# Power.net
KiCad netlist of a schematic drawn in Altium Designer
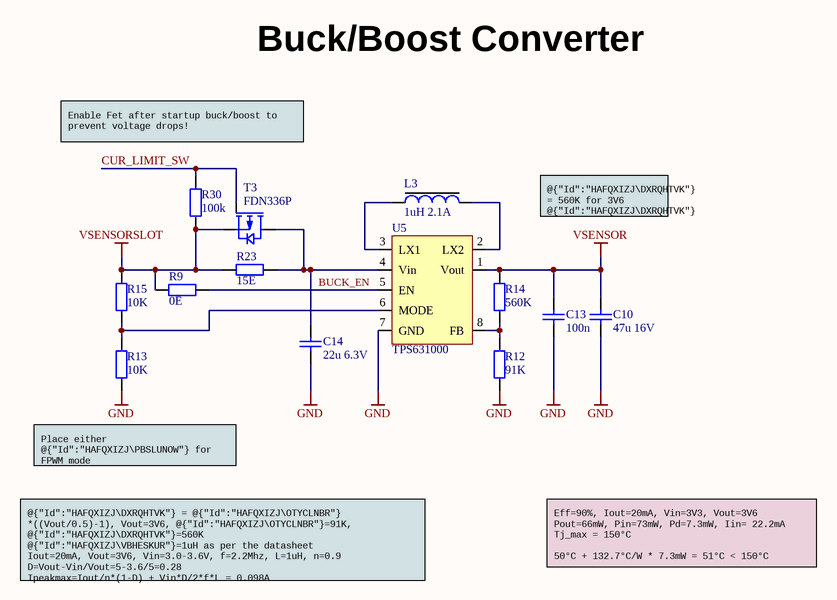
[diagram p0: Power.SchDoc]

(export (version "E")
  (design (tool "Eeschema 10.0.6"))
  (components
    (comp (ref "C10")
      (value "47u 16V")
      (footprint "CAPC3225X27N")
      (description "47uF 16V 20% X5R")
      (libsource (lib "DCI") (part "Capacitor_NP"))
    )
    (comp (ref "C13")
      (value "100n")
      (footprint "CAPC1608X09N")
      (description "100nF 50V 10% X7R")
      (libsource (lib "DCI") (part "Capacitor_NP"))
    )
    (comp (ref "C14")
      (value "22u 6.3V")
      (footprint "CAPC1608X09N")
      (description "22uF 20%  6.3V X5R")
      (libsource (lib "DCI") (part "Capacitor_NP"))
    )
    (comp (ref "L3")
      (value "1uH 2.1A")
      (footprint "IND-001G002-002")
      (description "Power inductor 2.1A")
      (libsource (lib "DCI") (part "Inductor"))
    )
    (comp (ref "R9")
      (value "0E")
      (footprint "RESC1608X13N")
      (description "0E 100mW, 1%")
      (libsource (lib "") (part "Resistor_2"))
    )
    (comp (ref "R12")
      (value "91K")
      (footprint "RESC1608X13N")
      (description "91k 0.06W 1%")
      (libsource (lib "") (part "Resistor_1"))
    )
    (comp (ref "R13")
      (value "10K")
      (footprint "RESC1608X13N")
      (description "10k 100mW, 1%")
      (libsource (lib "") (part "Resistor_1"))
    )
    (comp (ref "R14")
      (value "560K")
      (footprint "RESC1608X13N")
      (description "560kΩ 100mW 1%")
      (libsource (lib "DCI") (part "Resistor"))
    )
    (comp (ref "R15")
      (value "10K")
      (footprint "RESC1608X13N")
      (description "10k 100mW, 1%")
      (libsource (lib "") (part "Resistor_1"))
    )
    (comp (ref "R23")
      (value "15E")
      (footprint "RESC2013X14N")
      (description "15Ω 125mW 1%")
      (libsource (lib "") (part "Resistor_3"))
    )
    (comp (ref "R30")
      (value "100k")
      (footprint "RESC1608X13N")
      (description "100kΩ 100mW 1%")
      (libsource (lib "DCI") (part "Resistor"))
    )
    (comp (ref "T3")
      (value "FDN336P")
      (footprint "SOT95P245X110_GSD-3N")
      (description "20V 1.3A 200mΩ logic level")
      (libsource (lib "DCI") (part "P_Mosfet"))
    )
    (comp (ref "U5")
      (value "TPS631000")
      (footprint "SOT-501001-008")
      (description "Buck/boost 1.5-5.5V, 1A5")
      (libsource (lib "DCI") (part "SW_BUCK_BOOST_TPS631000"))
    )
  )
  (nets
    (net (code "1") (name "/BUCK_EN") (class "Default")
      (node (ref "R9") (pin "1") (pinfunction "1_1") (pintype "passive"))
      (node (ref "U5") (pin "5") (pinfunction "EN_5") (pintype "passive"))
    )
    (net (code "2") (name "/CUR_LIMIT_SW") (class "Default")
      (node (ref "R30") (pin "2") (pinfunction "2_2") (pintype "passive"))
      (node (ref "T3") (pin "G") (pinfunction "G_G") (pintype "passive"))
    )
    (net (code "3") (name "GND") (class "Default")
      (node (ref "C10") (pin "1") (pinfunction "1_1") (pintype "passive"))
      (node (ref "C13") (pin "1") (pinfunction "1_1") (pintype "passive"))
      (node (ref "C14") (pin "1") (pinfunction "1_1") (pintype "passive"))
      (node (ref "R12") (pin "1") (pinfunction "1_1") (pintype "passive"))
      (node (ref "R13") (pin "1") (pinfunction "1_1") (pintype "passive"))
      (node (ref "U5") (pin "7") (pinfunction "GND_7") (pintype "passive"))
    )
    (net (code "4") (name "Net-(U5-FB)") (class "Default")
      (node (ref "R12") (pin "2") (pinfunction "2_2") (pintype "passive"))
      (node (ref "R14") (pin "1") (pinfunction "1_1") (pintype "passive"))
      (node (ref "U5") (pin "8") (pinfunction "FB_8") (pintype "passive"))
    )
    (net (code "5") (name "Net-(U5-LX1)") (class "Default")
      (node (ref "L3") (pin "1") (pinfunction "1_1") (pintype "passive"))
      (node (ref "U5") (pin "3") (pinfunction "LX1_3") (pintype "power_in"))
    )
    (net (code "6") (name "Net-(U5-LX2)") (class "Default")
      (node (ref "L3") (pin "2") (pinfunction "2_2") (pintype "passive"))
      (node (ref "U5") (pin "2") (pinfunction "LX2_2") (pintype "power_in"))
    )
    (net (code "7") (name "Net-(U5-MODE)") (class "Default")
      (node (ref "R13") (pin "2") (pinfunction "2_2") (pintype "passive"))
      (node (ref "R15") (pin "1") (pinfunction "1_1") (pintype "passive"))
      (node (ref "U5") (pin "6") (pinfunction "MODE_6") (pintype "passive"))
    )
    (net (code "8") (name "Net-(U5-Vin)") (class "Default")
      (node (ref "C14") (pin "2") (pinfunction "2_2") (pintype "passive"))
      (node (ref "R23") (pin "2") (pinfunction "2_2") (pintype "passive"))
      (node (ref "T3") (pin "D") (pinfunction "D_D") (pintype "passive"))
      (node (ref "U5") (pin "4") (pinfunction "Vin_4") (pintype "power_in"))
    )
    (net (code "9") (name "VSENSOR") (class "Default")
      (node (ref "C10") (pin "2") (pinfunction "2_2") (pintype "passive"))
      (node (ref "C13") (pin "2") (pinfunction "2_2") (pintype "passive"))
      (node (ref "R14") (pin "2") (pinfunction "2_2") (pintype "passive"))
      (node (ref "U5") (pin "1") (pinfunction "Vout_1") (pintype "passive"))
    )
    (net (code "10") (name "VSENSORSLOT") (class "Default")
      (node (ref "R15") (pin "2") (pinfunction "2_2") (pintype "passive"))
      (node (ref "R23") (pin "1") (pinfunction "1_1") (pintype "passive"))
      (node (ref "R30") (pin "1") (pinfunction "1_1") (pintype "passive"))
      (node (ref "R9") (pin "2") (pinfunction "2_2") (pintype "passive"))
      (node (ref "T3") (pin "S") (pinfunction "S_S") (pintype "passive"))
    )
  )
)
